# frequency_divider_1_2.net
KiCad netlist of a schematic drawn in EAGLE
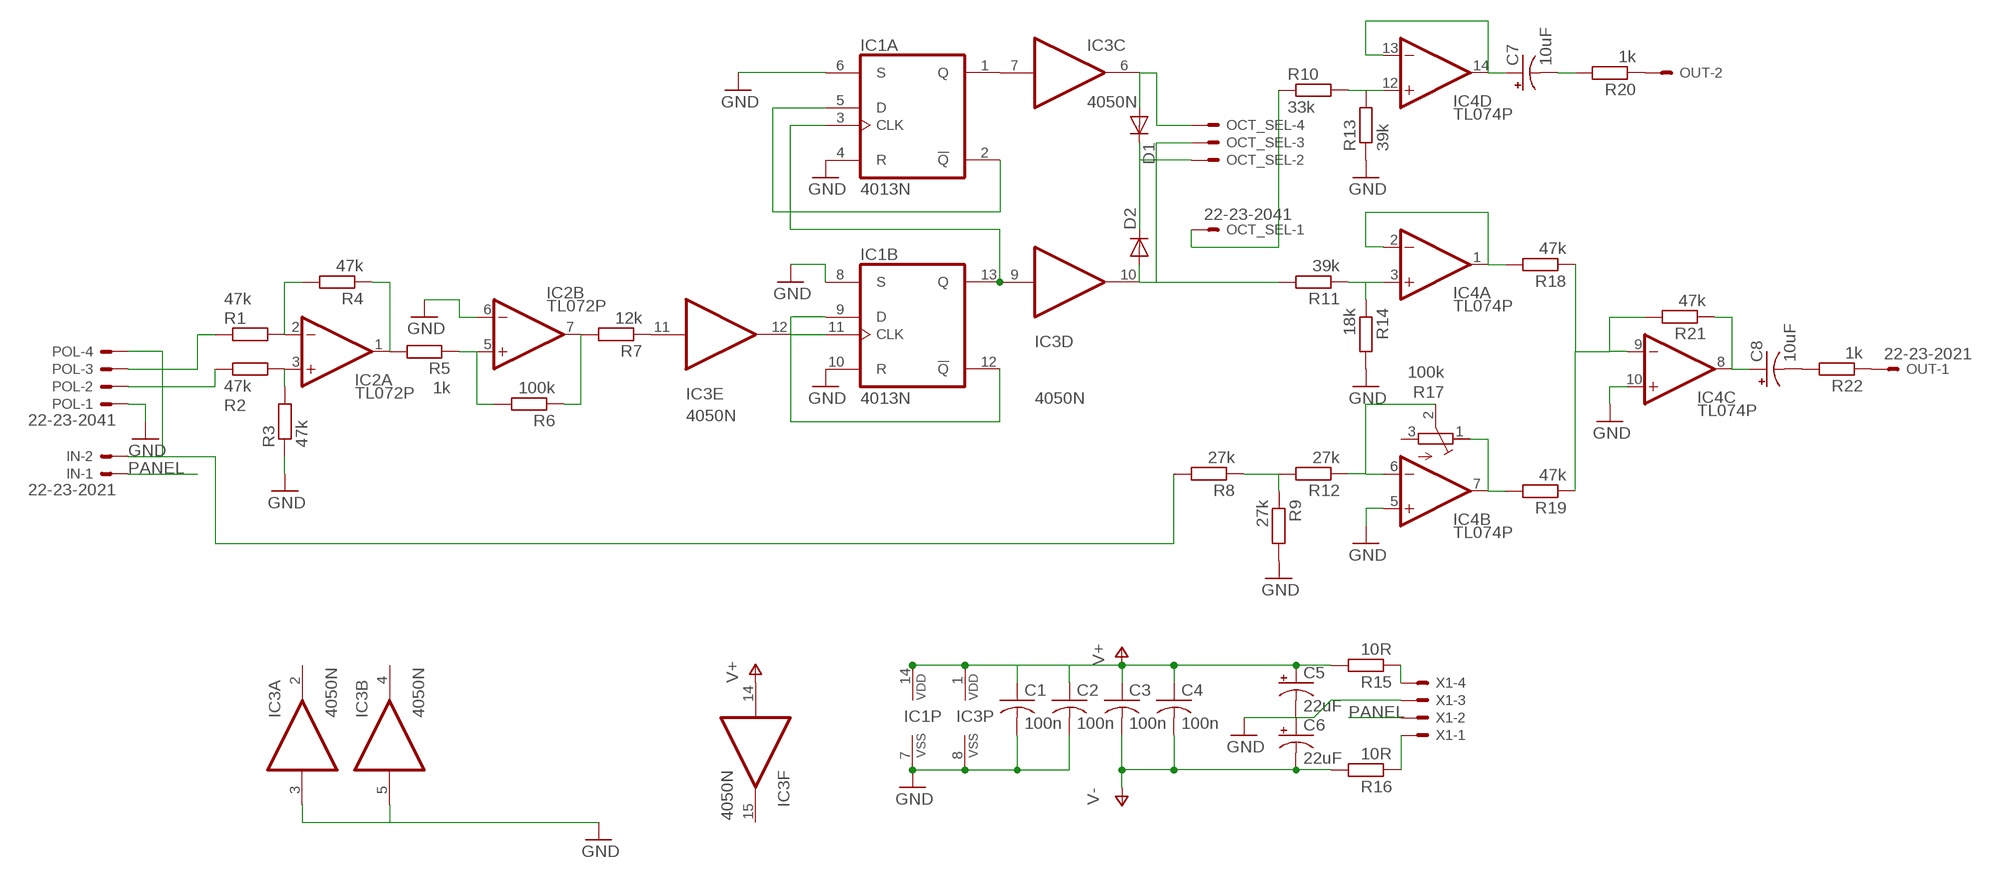
[diagram p0: schematic, sheet 1]

(export (version "E")
  (design (tool "Eeschema 10.0.6"))
  (components
    (comp (ref "C1")
      (value "100n")
      (footprint "eagle-import:C025-024X044")
      (libsource (lib "eagle-import") (part "C-US025-024X044"))
    )
    (comp (ref "C2")
      (value "100n")
      (footprint "eagle-import:C025-024X044")
      (libsource (lib "eagle-import") (part "C-US025-024X044"))
    )
    (comp (ref "C3")
      (value "100n")
      (footprint "eagle-import:C025-024X044")
      (libsource (lib "eagle-import") (part "C-US025-024X044"))
    )
    (comp (ref "C4")
      (value "100n")
      (footprint "eagle-import:C025-024X044")
      (libsource (lib "eagle-import") (part "C-US025-024X044"))
    )
    (comp (ref "C5")
      (value "22uF")
      (footprint "eagle-import:E2,5-5")
      (libsource (lib "eagle-import") (part "CPOL-USE2.5-5"))
    )
    (comp (ref "C6")
      (value "22uF")
      (footprint "eagle-import:E2,5-5")
      (libsource (lib "eagle-import") (part "CPOL-USE2.5-5"))
    )
    (comp (ref "C7")
      (value "10uF")
      (footprint "eagle-import:E2,5-5")
      (libsource (lib "eagle-import") (part "CPOL-USE2.5-5"))
    )
    (comp (ref "C8")
      (value "10uF")
      (footprint "eagle-import:E2,5-5")
      (libsource (lib "eagle-import") (part "CPOL-USE2.5-5"))
    )
    (comp (ref "D1")
      (value "DIODE-D-5")
      (footprint "eagle-import:D-5")
      (libsource (lib "eagle-import") (part "DIODE-D-5"))
    )
    (comp (ref "D2")
      (value "DIODE-D-5")
      (footprint "eagle-import:D-5")
      (libsource (lib "eagle-import") (part "DIODE-D-5"))
    )
    (comp (ref "IC1")
      (value "4013N")
      (footprint "eagle-import:DIL14")
      (libsource (lib "eagle-import") (part "4013N"))
    )
    (comp (ref "IC2")
      (value "TL072P")
      (footprint "eagle-import:DIL08")
      (libsource (lib "eagle-import") (part "TL072P"))
    )
    (comp (ref "IC3")
      (value "4050N")
      (footprint "eagle-import:DIL16")
      (libsource (lib "eagle-import") (part "4050N"))
    )
    (comp (ref "IC4")
      (value "TL074P")
      (footprint "eagle-import:DIL14")
      (libsource (lib "eagle-import") (part "TL074P"))
    )
    (comp (ref "IN")
      (value "22-23-2021")
      (footprint "eagle-import:22-23-2021")
      (fields (field (name "MF") "MOLEX"))
      (libsource (lib "eagle-import") (part "22-23-2021"))
    )
    (comp (ref "OCT_SEL")
      (value "22-23-2041")
      (footprint "eagle-import:22-23-2041")
      (fields (field (name "MF") "MOLEX"))
      (libsource (lib "eagle-import") (part "22-23-2041"))
    )
    (comp (ref "OUT")
      (value "22-23-2021")
      (footprint "eagle-import:22-23-2021")
      (fields (field (name "MF") "MOLEX"))
      (libsource (lib "eagle-import") (part "22-23-2021"))
    )
    (comp (ref "POL")
      (value "22-23-2041")
      (footprint "eagle-import:22-23-2041")
      (fields (field (name "MF") "MOLEX"))
      (libsource (lib "eagle-import") (part "22-23-2041"))
    )
    (comp (ref "R1")
      (value "47k")
      (footprint "eagle-import:0204_7")
      (libsource (lib "eagle-import") (part "R-EU_0204/7"))
    )
    (comp (ref "R2")
      (value "47k")
      (footprint "eagle-import:0204_7")
      (libsource (lib "eagle-import") (part "R-EU_0204/7"))
    )
    (comp (ref "R3")
      (value "47k")
      (footprint "eagle-import:0204_7")
      (libsource (lib "eagle-import") (part "R-EU_0204/7"))
    )
    (comp (ref "R4")
      (value "47k")
      (footprint "eagle-import:0204_7")
      (libsource (lib "eagle-import") (part "R-EU_0204/7"))
    )
    (comp (ref "R5")
      (value "1k")
      (footprint "eagle-import:0204_7")
      (libsource (lib "eagle-import") (part "R-EU_0204/7"))
    )
    (comp (ref "R6")
      (value "100k")
      (footprint "eagle-import:0204_7")
      (libsource (lib "eagle-import") (part "R-EU_0204/7"))
    )
    (comp (ref "R7")
      (value "12k")
      (footprint "eagle-import:0204_7")
      (libsource (lib "eagle-import") (part "R-EU_0204/7"))
    )
    (comp (ref "R8")
      (value "27k")
      (footprint "eagle-import:0204_7")
      (libsource (lib "eagle-import") (part "R-EU_0204/7"))
    )
    (comp (ref "R9")
      (value "27k")
      (footprint "eagle-import:0204_7")
      (libsource (lib "eagle-import") (part "R-EU_0204/7"))
    )
    (comp (ref "R10")
      (value "33k")
      (footprint "eagle-import:0204_7")
      (libsource (lib "eagle-import") (part "R-EU_0204/7"))
    )
    (comp (ref "R11")
      (value "39k")
      (footprint "eagle-import:0204_7")
      (libsource (lib "eagle-import") (part "resistor_R-EU_0204/7"))
    )
    (comp (ref "R12")
      (value "27k")
      (footprint "eagle-import:0204_7")
      (libsource (lib "eagle-import") (part "R-EU_0204/7"))
    )
    (comp (ref "R13")
      (value "39k")
      (footprint "eagle-import:0204_7")
      (libsource (lib "eagle-import") (part "R-EU_0204/7"))
    )
    (comp (ref "R14")
      (value "18k")
      (footprint "eagle-import:0204_7")
      (libsource (lib "eagle-import") (part "R-EU_0204/7"))
    )
    (comp (ref "R15")
      (value "10R")
      (footprint "eagle-import:0204_7")
      (libsource (lib "eagle-import") (part "R-EU_0204/7"))
    )
    (comp (ref "R16")
      (value "10R")
      (footprint "eagle-import:0204_7")
      (libsource (lib "eagle-import") (part "R-EU_0204/7"))
    )
    (comp (ref "R17")
      (value "100k")
      (footprint "eagle-import:RTRIMT93YA")
      (libsource (lib "eagle-import") (part "R-TRIMMT93YA"))
    )
    (comp (ref "R18")
      (value "47k")
      (footprint "eagle-import:0204_7")
      (libsource (lib "eagle-import") (part "R-EU_0204/7"))
    )
    (comp (ref "R19")
      (value "47k")
      (footprint "eagle-import:0204_7")
      (libsource (lib "eagle-import") (part "R-EU_0204/7"))
    )
    (comp (ref "R20")
      (value "1k")
      (footprint "eagle-import:0204_7")
      (libsource (lib "eagle-import") (part "R-EU_0204/7"))
    )
    (comp (ref "R21")
      (value "47k")
      (footprint "eagle-import:0204_7")
      (libsource (lib "eagle-import") (part "R-EU_0204/7"))
    )
    (comp (ref "R22")
      (value "1k")
      (footprint "eagle-import:0204_7")
      (libsource (lib "eagle-import") (part "R-EU_0204/7"))
    )
    (comp (ref "X1")
      (value "KK-156-4")
      (footprint "eagle-import:KK-156-4")
      (libsource (lib "eagle-import") (part "KK-156-4"))
    )
  )
  (nets
    (net (code "1") (name "/PANEL") (class "Default")
      (node (ref "IN") (pin "1") (pinfunction "S_1") (pintype "passive"))
      (node (ref "X1") (pin "2") (pinfunction "S_2") (pintype "passive"))
    )
    (net (code "2") (name "GND") (class "Default")
      (node (ref "C1") (pin "2") (pinfunction "2_2") (pintype "passive"))
      (node (ref "C2") (pin "2") (pinfunction "2_2") (pintype "passive"))
      (node (ref "C5") (pin "-") (pinfunction "-_-") (pintype "passive"))
      (node (ref "C6") (pin "+") (pinfunction "+_+") (pintype "passive"))
      (node (ref "IC1") (pin "10") (pinfunction "R_10") (pintype "input"))
      (node (ref "IC1") (pin "4") (pinfunction "R_4") (pintype "input"))
      (node (ref "IC1") (pin "6") (pinfunction "S_6") (pintype "input"))
      (node (ref "IC1") (pin "7") (pinfunction "VSS_7") (pintype "power_in"))
      (node (ref "IC1") (pin "8") (pinfunction "S_8") (pintype "input"))
      (node (ref "IC2") (pin "6") (pinfunction "-IN_6") (pintype "input"))
      (node (ref "IC3") (pin "3") (pinfunction "I_3") (pintype "input"))
      (node (ref "IC3") (pin "5") (pinfunction "I_5") (pintype "input"))
      (node (ref "IC3") (pin "8") (pinfunction "VSS_8") (pintype "power_in"))
      (node (ref "IC4") (pin "10") (pinfunction "+IN_10") (pintype "input"))
      (node (ref "IC4") (pin "5") (pinfunction "+IN_5") (pintype "input"))
      (node (ref "POL") (pin "1") (pinfunction "S_1") (pintype "passive"))
      (node (ref "R13") (pin "1") (pinfunction "1_1") (pintype "passive"))
      (node (ref "R14") (pin "2") (pinfunction "2_2") (pintype "passive"))
      (node (ref "R3") (pin "1") (pinfunction "1_1") (pintype "passive"))
      (node (ref "R9") (pin "2") (pinfunction "2_2") (pintype "passive"))
      (node (ref "X1") (pin "3") (pinfunction "S_3") (pintype "passive"))
    )
    (net (code "3") (name "Net-(C7-Pad-)") (class "Default")
      (node (ref "C7") (pin "-") (pinfunction "-_-") (pintype "passive"))
      (node (ref "R20") (pin "2") (pinfunction "2_2") (pintype "passive"))
    )
    (net (code "4") (name "Net-(C8-Pad-)") (class "Default")
      (node (ref "C8") (pin "-") (pinfunction "-_-") (pintype "passive"))
      (node (ref "R22") (pin "2") (pinfunction "2_2") (pintype "passive"))
    )
    (net (code "5") (name "Net-(IC1A-CLK)") (class "Default")
      (node (ref "IC1") (pin "13") (pinfunction "Q_13") (pintype "output"))
      (node (ref "IC1") (pin "3") (pinfunction "CLK_3") (pintype "input"))
      (node (ref "IC3") (pin "9") (pinfunction "I_9") (pintype "input"))
    )
    (net (code "6") (name "Net-(IC1A-D)") (class "Default")
      (node (ref "IC1") (pin "2") (pinfunction "~{Q}_2") (pintype "output"))
      (node (ref "IC1") (pin "5") (pinfunction "D_5") (pintype "input"))
    )
    (net (code "7") (name "Net-(IC1A-Q)") (class "Default")
      (node (ref "IC1") (pin "1") (pinfunction "Q_1") (pintype "output"))
      (node (ref "IC3") (pin "7") (pinfunction "I_7") (pintype "input"))
    )
    (net (code "8") (name "Net-(IC1B-CLK)") (class "Default")
      (node (ref "IC1") (pin "11") (pinfunction "CLK_11") (pintype "input"))
      (node (ref "IC3") (pin "12") (pinfunction "O_12") (pintype "output"))
    )
    (net (code "9") (name "Net-(IC1B-D)") (class "Default")
      (node (ref "IC1") (pin "12") (pinfunction "~{Q}_12") (pintype "output"))
      (node (ref "IC1") (pin "9") (pinfunction "D_9") (pintype "input"))
    )
    (net (code "10") (name "Net-(IC2A-+IN)") (class "Default")
      (node (ref "IC2") (pin "3") (pinfunction "+IN_3") (pintype "input"))
      (node (ref "R2") (pin "2") (pinfunction "2_2") (pintype "passive"))
      (node (ref "R3") (pin "2") (pinfunction "2_2") (pintype "passive"))
    )
    (net (code "11") (name "Net-(IC2A--IN)") (class "Default")
      (node (ref "IC2") (pin "2") (pinfunction "-IN_2") (pintype "input"))
      (node (ref "R1") (pin "2") (pinfunction "2_2") (pintype "passive"))
      (node (ref "R4") (pin "2") (pinfunction "2_2") (pintype "passive"))
    )
    (net (code "12") (name "Net-(IC2A-OUT)") (class "Default")
      (node (ref "IC2") (pin "1") (pinfunction "OUT_1") (pintype "output"))
      (node (ref "R4") (pin "1") (pinfunction "1_1") (pintype "passive"))
      (node (ref "R5") (pin "2") (pinfunction "2_2") (pintype "passive"))
    )
    (net (code "13") (name "Net-(IC2B-+IN)") (class "Default")
      (node (ref "IC2") (pin "5") (pinfunction "+IN_5") (pintype "input"))
      (node (ref "R5") (pin "1") (pinfunction "1_1") (pintype "passive"))
      (node (ref "R6") (pin "2") (pinfunction "2_2") (pintype "passive"))
    )
    (net (code "14") (name "Net-(IC2B-OUT)") (class "Default")
      (node (ref "IC2") (pin "7") (pinfunction "OUT_7") (pintype "output"))
      (node (ref "R6") (pin "1") (pinfunction "1_1") (pintype "passive"))
      (node (ref "R7") (pin "2") (pinfunction "2_2") (pintype "passive"))
    )
    (net (code "15") (name "Net-(IC3C-O)") (class "Default")
      (node (ref "D1") (pin "A") (pinfunction "A_A") (pintype "passive"))
      (node (ref "IC3") (pin "6") (pinfunction "O_6") (pintype "output"))
      (node (ref "OCT_SEL") (pin "4") (pinfunction "S_4") (pintype "passive"))
    )
    (net (code "16") (name "Net-(IC3D-O)") (class "Default")
      (node (ref "D2") (pin "A") (pinfunction "A_A") (pintype "passive"))
      (node (ref "IC3") (pin "10") (pinfunction "O_10") (pintype "output"))
      (node (ref "OCT_SEL") (pin "3") (pinfunction "S_3") (pintype "passive"))
      (node (ref "R11") (pin "2") (pinfunction "2_2") (pintype "passive"))
    )
    (net (code "17") (name "Net-(IC3E-I)") (class "Default")
      (node (ref "IC3") (pin "11") (pinfunction "I_11") (pintype "input"))
      (node (ref "R7") (pin "1") (pinfunction "1_1") (pintype "passive"))
    )
    (net (code "18") (name "Net-(IC4A-+IN)") (class "Default")
      (node (ref "IC4") (pin "3") (pinfunction "+IN_3") (pintype "input"))
      (node (ref "R11") (pin "1") (pinfunction "1_1") (pintype "passive"))
      (node (ref "R14") (pin "1") (pinfunction "1_1") (pintype "passive"))
    )
    (net (code "19") (name "Net-(IC4A--IN)") (class "Default")
      (node (ref "IC4") (pin "1") (pinfunction "OUT_1") (pintype "output"))
      (node (ref "IC4") (pin "2") (pinfunction "-IN_2") (pintype "input"))
      (node (ref "R18") (pin "2") (pinfunction "2_2") (pintype "passive"))
    )
    (net (code "20") (name "Net-(IC4B--IN)") (class "Default")
      (node (ref "IC4") (pin "6") (pinfunction "-IN_6") (pintype "input"))
      (node (ref "R12") (pin "1") (pinfunction "1_1") (pintype "passive"))
      (node (ref "R17") (pin "2") (pinfunction "S_2") (pintype "passive"))
    )
    (net (code "21") (name "Net-(IC4B-OUT)") (class "Default")
      (node (ref "IC4") (pin "7") (pinfunction "OUT_7") (pintype "output"))
      (node (ref "R17") (pin "1") (pinfunction "A_1") (pintype "passive"))
      (node (ref "R19") (pin "2") (pinfunction "2_2") (pintype "passive"))
    )
    (net (code "22") (name "Net-(IC4C--IN)") (class "Default")
      (node (ref "IC4") (pin "9") (pinfunction "-IN_9") (pintype "input"))
      (node (ref "R18") (pin "1") (pinfunction "1_1") (pintype "passive"))
      (node (ref "R19") (pin "1") (pinfunction "1_1") (pintype "passive"))
      (node (ref "R21") (pin "2") (pinfunction "2_2") (pintype "passive"))
    )
    (net (code "23") (name "Net-(IC4C-OUT)") (class "Default")
      (node (ref "C8") (pin "+") (pinfunction "+_+") (pintype "passive"))
      (node (ref "IC4") (pin "8") (pinfunction "OUT_8") (pintype "output"))
      (node (ref "R21") (pin "1") (pinfunction "1_1") (pintype "passive"))
    )
    (net (code "24") (name "Net-(IC4D-+IN)") (class "Default")
      (node (ref "IC4") (pin "12") (pinfunction "+IN_12") (pintype "input"))
      (node (ref "R10") (pin "2") (pinfunction "2_2") (pintype "passive"))
      (node (ref "R13") (pin "2") (pinfunction "2_2") (pintype "passive"))
    )
    (net (code "25") (name "Net-(IC4D--IN)") (class "Default")
      (node (ref "C7") (pin "+") (pinfunction "+_+") (pintype "passive"))
      (node (ref "IC4") (pin "13") (pinfunction "-IN_13") (pintype "input"))
      (node (ref "IC4") (pin "14") (pinfunction "OUT_14") (pintype "output"))
    )
    (net (code "26") (name "Net-(INB-S)") (class "Default")
      (node (ref "IN") (pin "2") (pinfunction "S_2") (pintype "passive"))
      (node (ref "POL") (pin "4") (pinfunction "S_4") (pintype "passive"))
      (node (ref "R8") (pin "2") (pinfunction "2_2") (pintype "passive"))
    )
    (net (code "27") (name "Net-(OCT_SELA-S)") (class "Default")
      (node (ref "OCT_SEL") (pin "1") (pinfunction "S_1") (pintype "passive"))
      (node (ref "R10") (pin "1") (pinfunction "1_1") (pintype "passive"))
    )
    (net (code "28") (name "Net-(OCT_SELB-S)") (class "Default")
      (node (ref "D1") (pin "C") (pinfunction "C_C") (pintype "passive"))
      (node (ref "D2") (pin "C") (pinfunction "C_C") (pintype "passive"))
      (node (ref "OCT_SEL") (pin "2") (pinfunction "S_2") (pintype "passive"))
    )
    (net (code "29") (name "Net-(OUTA-S)") (class "Default")
      (node (ref "OUT") (pin "1") (pinfunction "S_1") (pintype "passive"))
      (node (ref "R22") (pin "1") (pinfunction "1_1") (pintype "passive"))
    )
    (net (code "30") (name "Net-(OUTB-S)") (class "Default")
      (node (ref "OUT") (pin "2") (pinfunction "S_2") (pintype "passive"))
      (node (ref "R20") (pin "1") (pinfunction "1_1") (pintype "passive"))
    )
    (net (code "31") (name "Net-(POLB-S)") (class "Default")
      (node (ref "POL") (pin "2") (pinfunction "S_2") (pintype "passive"))
      (node (ref "R2") (pin "1") (pinfunction "1_1") (pintype "passive"))
    )
    (net (code "32") (name "Net-(POLC-S)") (class "Default")
      (node (ref "POL") (pin "3") (pinfunction "S_3") (pintype "passive"))
      (node (ref "R1") (pin "1") (pinfunction "1_1") (pintype "passive"))
    )
    (net (code "33") (name "Net-(R12-Pad2)") (class "Default")
      (node (ref "R12") (pin "2") (pinfunction "2_2") (pintype "passive"))
      (node (ref "R8") (pin "1") (pinfunction "1_1") (pintype "passive"))
      (node (ref "R9") (pin "1") (pinfunction "1_1") (pintype "passive"))
    )
    (net (code "34") (name "Net-(X1A-S)") (class "Default")
      (node (ref "R16") (pin "1") (pinfunction "1_1") (pintype "passive"))
      (node (ref "X1") (pin "1") (pinfunction "S_1") (pintype "passive"))
    )
    (net (code "35") (name "Net-(X1D-S)") (class "Default")
      (node (ref "R15") (pin "1") (pinfunction "1_1") (pintype "passive"))
      (node (ref "X1") (pin "4") (pinfunction "S_4") (pintype "passive"))
    )
    (net (code "36") (name "V+") (class "Default")
      (node (ref "C1") (pin "1") (pinfunction "1_1") (pintype "passive"))
      (node (ref "C2") (pin "1") (pinfunction "1_1") (pintype "passive"))
      (node (ref "C3") (pin "1") (pinfunction "1_1") (pintype "passive"))
      (node (ref "C4") (pin "1") (pinfunction "1_1") (pintype "passive"))
      (node (ref "C5") (pin "+") (pinfunction "+_+") (pintype "passive"))
      (node (ref "IC1") (pin "14") (pinfunction "VDD_14") (pintype "power_in"))
      (node (ref "IC3") (pin "1") (pinfunction "VDD_1") (pintype "power_in"))
      (node (ref "IC3") (pin "14") (pinfunction "I_14") (pintype "input"))
      (node (ref "R15") (pin "2") (pinfunction "2_2") (pintype "passive"))
    )
    (net (code "37") (name "V-") (class "Default")
      (node (ref "C3") (pin "2") (pinfunction "2_2") (pintype "passive"))
      (node (ref "C4") (pin "2") (pinfunction "2_2") (pintype "passive"))
      (node (ref "C6") (pin "-") (pinfunction "-_-") (pintype "passive"))
      (node (ref "R16") (pin "2") (pinfunction "2_2") (pintype "passive"))
    )
    (net (code "38") (name "unconnected-(IC3A-O-Pad2)") (class "Default")
      (node (ref "IC3") (pin "2") (pinfunction "O_2") (pintype "output"))
    )
    (net (code "39") (name "unconnected-(IC3B-O-Pad4)") (class "Default")
      (node (ref "IC3") (pin "4") (pinfunction "O_4") (pintype "output"))
    )
    (net (code "40") (name "unconnected-(IC3F-O-Pad15)") (class "Default")
      (node (ref "IC3") (pin "15") (pinfunction "O_15") (pintype "output"))
    )
    (net (code "41") (name "unconnected-(R17-E-Pad3)") (class "Default")
      (node (ref "R17") (pin "3") (pinfunction "E_3") (pintype "passive"))
    )
  )
)
